# Power_Schematic.net
KiCad netlist of a schematic drawn in Altium Designer
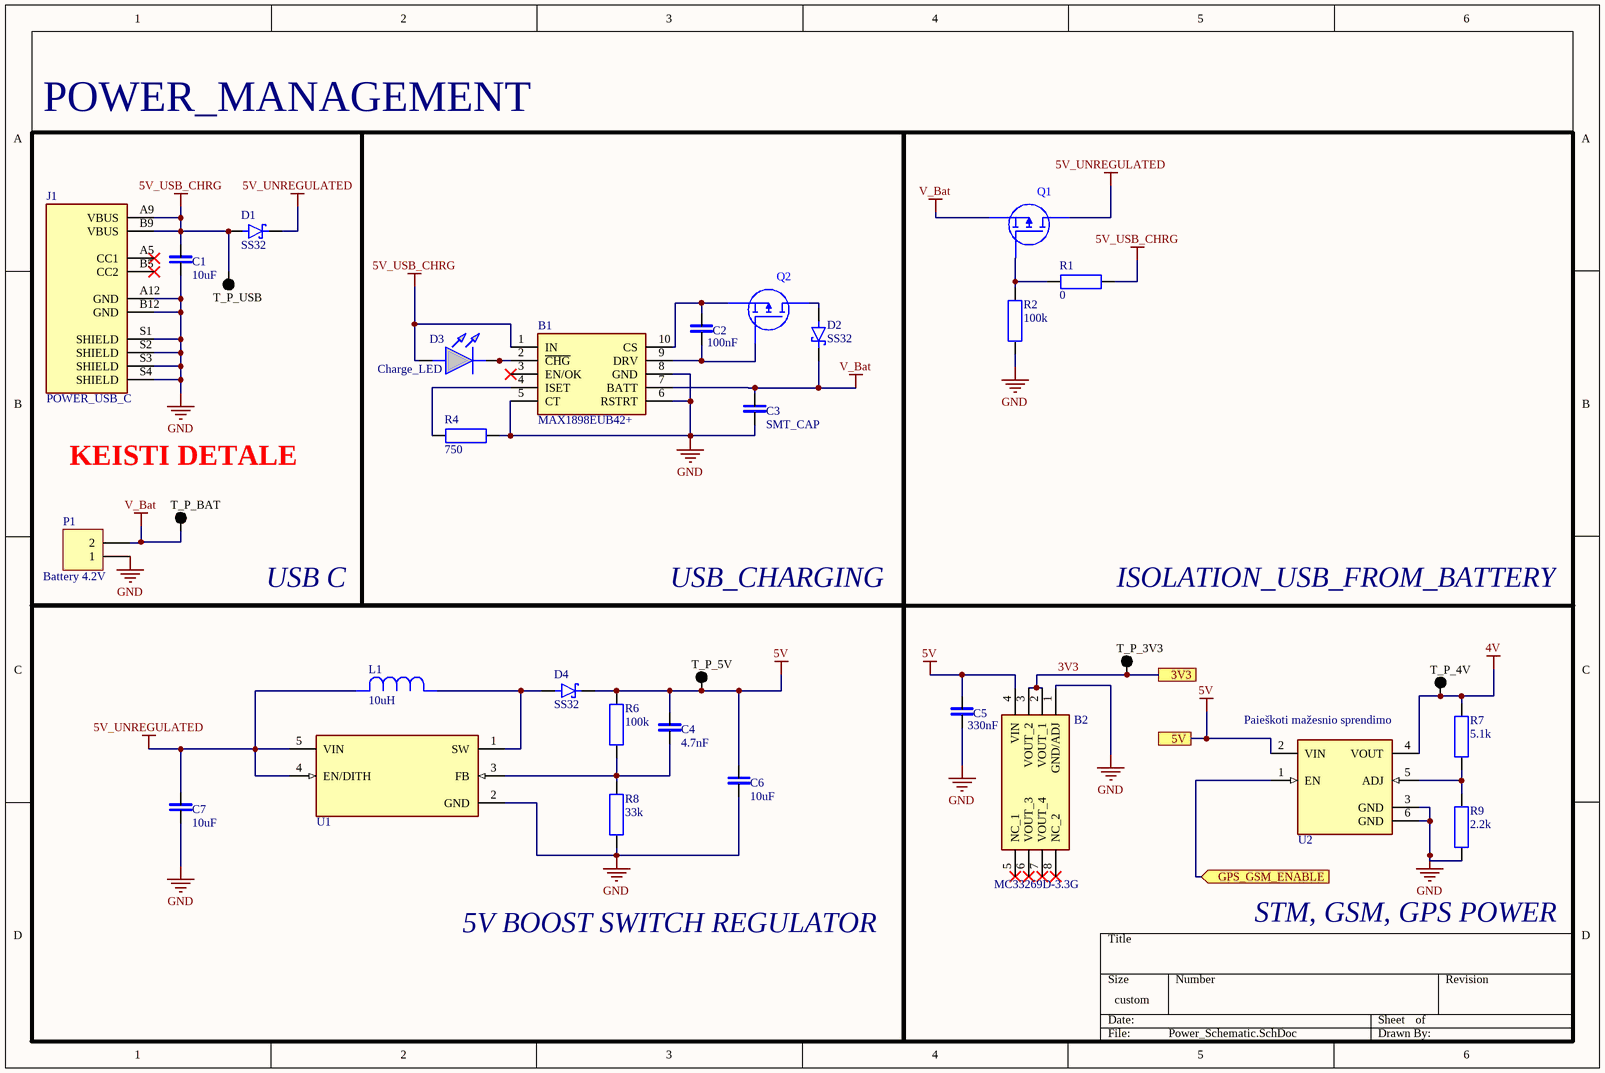
[diagram p0: Power_Schematic.SchDoc]

(export (version "E")
  (design (tool "Eeschema 10.0.6"))
  (components
    (comp (ref "B1")
      (value "MAX1898EUB42+")
      (footprint "MAX1898EUB42")
      (description "Part: MAX1898EUB42+ BATT CHARGER, LI-ION, 4.2V")
      (fields (field (name "MOUSER PART NUMBER") "700-MAX1898EUB42"))
      (libsource (lib "IC") (part "MAX1898EUB42+"))
    )
    (comp (ref "B2")
      (value "MC33269D-3.3G")
      (footprint "3V3Voltage_MC33269D-3.3G")
      (description "Voltage regulator,Part: MC33269D-3.3G, Low Dropout Voltage Regulator, 0.8A 3.3")
      (fields (field (name "MOUSER PART NUMBER") "863-MC33269D-3.3G"))
      (libsource (lib "IC") (part "LDO3V3"))
    )
    (comp (ref "C1")
      (value "10uF")
      (footprint "CAP_0805")
      (fields (field (name "MP") "LD051A270KAB2A"))
      (libsource (lib "Passive_Components") (part "SMT_CAP"))
    )
    (comp (ref "C2")
      (value "100nF")
      (footprint "CAP_0805")
      (fields (field (name "MP") "LD051A270KAB2A"))
      (libsource (lib "Passive_Components") (part "SMT_CAP"))
    )
    (comp (ref "C3")
      (value "SMT_CAP")
      (footprint "CAP_0805")
      (fields (field (name "MP") "LD051A270KAB2A"))
      (libsource (lib "Passive_Components") (part "SMT_CAP"))
    )
    (comp (ref "C4")
      (value "4.7nF")
      (footprint "CAP_0805")
      (fields (field (name "MP") "LD051A270KAB2A"))
      (libsource (lib "Passive_Components") (part "SMT_CAP"))
    )
    (comp (ref "C5")
      (value "330nF")
      (footprint "CAP_0805")
      (fields (field (name "MP") "LD051A270KAB2A"))
      (libsource (lib "Passive_Components") (part "SMT_CAP"))
    )
    (comp (ref "C6")
      (value "10uF")
      (footprint "CAP_0805")
      (fields (field (name "MP") "LD051A270KAB2A"))
      (libsource (lib "Passive_Components") (part "SMT_CAP"))
    )
    (comp (ref "C7")
      (value "10uF")
      (footprint "CAP_0805")
      (fields (field (name "MP") "LD051A270KAB2A"))
      (libsource (lib "Passive_Components") (part "SMT_CAP"))
    )
    (comp (ref "D1")
      (value "SS32")
      (footprint "POWER_SCHOTKY_3A")
      (description "Part: SS32")
      (fields (field (name "MF") "ON Semiconductor"))
      (libsource (lib "Diodes") (part "POWER_SCHOTKY_3A"))
    )
    (comp (ref "D2")
      (value "SS32")
      (footprint "POWER_SCHOTKY_3A")
      (description "Part: SS32")
      (fields (field (name "MF") "ON Semiconductor"))
      (libsource (lib "Diodes") (part "POWER_SCHOTKY_3A"))
    )
    (comp (ref "D3")
      (value "Charge_LED")
      (footprint "LED_0805")
      (description "Part: HSMH-C170")
      (fields
        (field (name "MANUFACTURER_PART_NUMBER") "HSMH-C170")
        (field (name "MOUSER PART NUMBER") "630-HSMH-C170")
      )
      (libsource (lib "Diodes") (part "LED"))
    )
    (comp (ref "D4")
      (value "SS32")
      (footprint "POWER_SCHOTKY_3A")
      (description "Part: SS32")
      (fields (field (name "MF") "ON Semiconductor"))
      (libsource (lib "Diodes") (part "POWER_SCHOTKY_3A"))
    )
    (comp (ref "J1")
      (value "POWER_USB_C")
      (footprint "POWER_USB_C")
      (description "Type C USB Charging Connector part name : USB4515-GF-A_REVA")
      (fields
        (field (name "MF") "Global Connector Technology")
        (field (name "DIGI-KEY_PART_NUMBER") "2073-USB4515-GF-ATR-ND")
      )
      (libsource (lib "Connectors") (part "POWER_USB_C"))
    )
    (comp (ref "L1")
      (value "10uH")
      (footprint "MCSD54-4R7MU")
      (description "Part: MCSD54-4R7MU")
      (fields
        (field (name "MANUFACTURER_PART_NUMBER") "MCSD54-4R7MU")
        (field (name "COPYRIGHT") "Copyright (C) 2023 Ultra Librarian. All rights reserved.")
      )
      (libsource (lib "Passive_Components") (part "IND"))
    )
    (comp (ref "P1")
      (value "Battery 4.2V")
      (footprint "HDR1X2")
      (description "Header, 2-Pin")
      (fields (field (name "PUBLISHER") "Altium Limited"))
      (libsource (lib "Miscellaneous Connectors") (part "Header 2"))
    )
    (comp (ref "Q1")
      (value "MOSFET Pch -45V -4.5A")
      (footprint "P_CHANNEL_POWER_RD3H045SPTL1")
      (description "Part: RD3H045SPTL1")
      (fields
        (field (name "MANUFACTURER_PART_NUMBER") "RD3H045SPTL1")
        (field (name "MOUSER_PART_NUMBER") "755-RD3H045SPTL1")
      )
      (libsource (lib "Transistors") (part "P_CHANNEL_POWER 4.5A RD3H045SPTL1"))
    )
    (comp (ref "Q2")
      (value "MOSFET Pch -45V -4.5A")
      (footprint "P_CHANNEL_POWER_RD3H045SPTL1")
      (description "Part: RD3H045SPTL1")
      (fields
        (field (name "MANUFACTURER_PART_NUMBER") "RD3H045SPTL1")
        (field (name "MOUSER_PART_NUMBER") "755-RD3H045SPTL1")
      )
      (libsource (lib "Transistors") (part "P_CHANNEL_POWER 4.5A RD3H045SPTL1"))
    )
    (comp (ref "R1")
      (value "0")
      (footprint "RES_0805")
      (fields
        (field (name "MP") "2-2176053-0")
        (field (name "TOLERANCE") "1%")
        (field (name "MF") "TE Connectivity")
      )
      (libsource (lib "Passive_Components") (part "SMT_RES"))
    )
    (comp (ref "R2")
      (value "100k")
      (footprint "RES_0805")
      (fields
        (field (name "MP") "2-2176053-0")
        (field (name "TOLERANCE") "1%")
        (field (name "MF") "TE Connectivity")
      )
      (libsource (lib "Passive_Components") (part "SMT_RES"))
    )
    (comp (ref "R4")
      (value "750")
      (footprint "RES_0805")
      (fields
        (field (name "MP") "2-2176053-0")
        (field (name "TOLERANCE") "1%")
        (field (name "MF") "TE Connectivity")
      )
      (libsource (lib "Passive_Components") (part "SMT_RES"))
    )
    (comp (ref "R6")
      (value "100k")
      (footprint "RES_0805")
      (fields
        (field (name "MP") "2-2176053-0")
        (field (name "TOLERANCE") "1%")
        (field (name "MF") "TE Connectivity")
      )
      (libsource (lib "Passive_Components") (part "SMT_RES"))
    )
    (comp (ref "R7")
      (value "5.1k")
      (footprint "RES_0805")
      (fields
        (field (name "MP") "2-2176053-0")
        (field (name "TOLERANCE") "1%")
        (field (name "MF") "TE Connectivity")
      )
      (libsource (lib "Passive_Components") (part "SMT_RES"))
    )
    (comp (ref "R8")
      (value "33k")
      (footprint "RES_0805")
      (fields
        (field (name "MP") "2-2176053-0")
        (field (name "TOLERANCE") "1%")
        (field (name "MF") "TE Connectivity")
      )
      (libsource (lib "Passive_Components") (part "SMT_RES"))
    )
    (comp (ref "R9")
      (value "2.2k")
      (footprint "RES_0805")
      (fields
        (field (name "MP") "2-2176053-0")
        (field (name "TOLERANCE") "1%")
        (field (name "MF") "TE Connectivity")
      )
      (libsource (lib "Passive_Components") (part "SMT_RES"))
    )
    (comp (ref "T_P1")
      (value "T_P_USB")
      (footprint "T_P")
      (description "Test_point")
      (libsource (lib "Extras") (part "T_P"))
    )
    (comp (ref "T_P2")
      (value "T_P_BAT")
      (footprint "T_P")
      (description "Test_point")
      (libsource (lib "Extras") (part "T_P"))
    )
    (comp (ref "T_P3")
      (value "T_P_3V3")
      (footprint "T_P")
      (description "Test_point")
      (libsource (lib "Extras") (part "T_P"))
    )
    (comp (ref "T_P4")
      (value "T_P_5V")
      (footprint "T_P")
      (description "Test_point")
      (libsource (lib "Extras") (part "T_P"))
    )
    (comp (ref "T_P5")
      (value "T_P_4V")
      (footprint "T_P")
      (description "Test_point")
      (libsource (lib "Extras") (part "T_P"))
    )
    (comp (ref "U1")
      (value "Switch Voltage Regulator MIC2250-1YD5-TR")
      (footprint "Switching_MIC2250-1YD5-TR")
      (description "Part: MIC2250-1YD5-TR\r\n2.5V to 5.5 V input \r\n1.24V to 32V output")
      (libsource (lib "IC") (part "Switch Voltage Regulator MIC2250-1YD5-TR"))
    )
    (comp (ref "U2")
      (value "1.24V-5V MIC37252WR")
      (footprint "1V24_5V_MIC37252WR")
      (description "Part: MIC37252WR")
      (libsource (lib "IC") (part "1.24V-5V MIC37252WR"))
    )
  )
  (nets
    (net (code "1") (name "/3V3") (class "Default")
      (node (ref "B2") (pin "2") (pinfunction "VOUT_1_2") (pintype "passive"))
      (node (ref "B2") (pin "3") (pinfunction "VOUT_2_3") (pintype "passive"))
      (node (ref "T_P3") (pin "1") (pintype "passive"))
    )
    (net (code "2") (name "/GPS_GSM_ENABLE") (class "Default")
      (node (ref "U2") (pin "1") (pinfunction "EN_1") (pintype "input"))
    )
    (net (code "3") (name "4V") (class "Default")
      (node (ref "R7") (pin "2") (pinfunction "2_2") (pintype "passive"))
      (node (ref "T_P5") (pin "1") (pintype "passive"))
      (node (ref "U2") (pin "4") (pinfunction "VOUT_4") (pintype "power_in"))
    )
    (net (code "4") (name "5V") (class "Default")
      (node (ref "B2") (pin "4") (pinfunction "VIN_4") (pintype "passive"))
      (node (ref "C4") (pin "2") (pinfunction "2_2") (pintype "passive"))
      (node (ref "C5") (pin "2") (pinfunction "2_2") (pintype "passive"))
      (node (ref "C6") (pin "2") (pinfunction "2_2") (pintype "passive"))
      (node (ref "D4") (pin "C") (pinfunction "K_C") (pintype "passive"))
      (node (ref "R6") (pin "2") (pinfunction "2_2") (pintype "passive"))
      (node (ref "T_P4") (pin "1") (pintype "passive"))
      (node (ref "U2") (pin "2") (pinfunction "VIN_2") (pintype "power_in"))
    )
    (net (code "5") (name "5V_UNREGULATED") (class "Default")
      (node (ref "C7") (pin "2") (pinfunction "2_2") (pintype "passive"))
      (node (ref "D1") (pin "C") (pinfunction "K_C") (pintype "passive"))
      (node (ref "L1") (pin "2") (pinfunction "2_2") (pintype "passive"))
      (node (ref "Q1") (pin "2") (pinfunction "D_2") (pintype "passive"))
      (node (ref "U1") (pin "4") (pinfunction "EN/DITH_4") (pintype "input"))
      (node (ref "U1") (pin "5") (pinfunction "VIN_5") (pintype "power_in"))
    )
    (net (code "6") (name "5V_USB_CHRG") (class "Default")
      (node (ref "B1") (pin "1") (pinfunction "IN_1") (pintype "passive"))
      (node (ref "C1") (pin "2") (pinfunction "2_2") (pintype "passive"))
      (node (ref "D1") (pin "A") (pinfunction "A_A") (pintype "passive"))
      (node (ref "D3") (pin "2") (pinfunction "A_2") (pintype "passive"))
      (node (ref "J1") (pin "A9") (pinfunction "VBUS_A9") (pintype "power_in"))
      (node (ref "J1") (pin "B9") (pinfunction "VBUS_B9") (pintype "power_in"))
      (node (ref "R1") (pin "2") (pinfunction "2_2") (pintype "passive"))
      (node (ref "T_P1") (pin "1") (pintype "passive"))
    )
    (net (code "7") (name "GND") (class "Default")
      (node (ref "B1") (pin "5") (pinfunction "CT_5") (pintype "passive"))
      (node (ref "B1") (pin "6") (pinfunction "RSTRT_6") (pintype "passive"))
      (node (ref "B1") (pin "8") (pinfunction "GND_8") (pintype "passive"))
      (node (ref "B2") (pin "1") (pinfunction "GND/ADJ_1") (pintype "passive"))
      (node (ref "C1") (pin "1") (pinfunction "1_1") (pintype "passive"))
      (node (ref "C3") (pin "1") (pinfunction "1_1") (pintype "passive"))
      (node (ref "C5") (pin "1") (pinfunction "1_1") (pintype "passive"))
      (node (ref "C6") (pin "1") (pinfunction "1_1") (pintype "passive"))
      (node (ref "C7") (pin "1") (pinfunction "1_1") (pintype "passive"))
      (node (ref "J1") (pin "A12") (pinfunction "GND_A12") (pintype "power_in"))
      (node (ref "J1") (pin "B12") (pinfunction "GND_B12") (pintype "power_in"))
      (node (ref "J1") (pin "S1") (pinfunction "SHIELD_S1") (pintype "power_in"))
      (node (ref "J1") (pin "S2") (pinfunction "SHIELD_S2") (pintype "power_in"))
      (node (ref "J1") (pin "S3") (pinfunction "SHIELD_S3") (pintype "power_in"))
      (node (ref "J1") (pin "S4") (pinfunction "SHIELD_S4") (pintype "power_in"))
      (node (ref "P1") (pin "1") (pinfunction "1_1") (pintype "passive"))
      (node (ref "R2") (pin "1") (pinfunction "1_1") (pintype "passive"))
      (node (ref "R4") (pin "2") (pinfunction "2_2") (pintype "passive"))
      (node (ref "R8") (pin "1") (pinfunction "1_1") (pintype "passive"))
      (node (ref "R9") (pin "1") (pinfunction "1_1") (pintype "passive"))
      (node (ref "U1") (pin "2") (pinfunction "GND_2") (pintype "power_in"))
      (node (ref "U2") (pin "3") (pinfunction "GND_3") (pintype "power_in"))
      (node (ref "U2") (pin "6") (pinfunction "GND_6") (pintype "power_in"))
    )
    (net (code "8") (name "Net-(B1-CS)") (class "Default")
      (node (ref "B1") (pin "10") (pinfunction "CS_10") (pintype "passive"))
      (node (ref "C2") (pin "2") (pinfunction "2_2") (pintype "passive"))
      (node (ref "Q2") (pin "3") (pinfunction "S_3") (pintype "passive"))
    )
    (net (code "9") (name "Net-(B1-DRV)") (class "Default")
      (node (ref "B1") (pin "9") (pinfunction "DRV_9") (pintype "passive"))
      (node (ref "C2") (pin "1") (pinfunction "1_1") (pintype "passive"))
      (node (ref "Q2") (pin "1") (pinfunction "G_1") (pintype "passive"))
    )
    (net (code "10") (name "Net-(B1-ISET)") (class "Default")
      (node (ref "B1") (pin "4") (pinfunction "ISET_4") (pintype "passive"))
      (node (ref "R4") (pin "1") (pinfunction "1_1") (pintype "passive"))
    )
    (net (code "11") (name "Net-(B1-~{CHG})") (class "Default")
      (node (ref "B1") (pin "2") (pinfunction "~{CHG}_2") (pintype "passive"))
      (node (ref "D3") (pin "1") (pinfunction "K_1") (pintype "passive"))
    )
    (net (code "12") (name "Net-(Q1-G)") (class "Default")
      (node (ref "Q1") (pin "1") (pinfunction "G_1") (pintype "passive"))
      (node (ref "R1") (pin "1") (pinfunction "1_1") (pintype "passive"))
      (node (ref "R2") (pin "2") (pinfunction "2_2") (pintype "passive"))
    )
    (net (code "13") (name "Net-(Q2-D)") (class "Default")
      (node (ref "D2") (pin "A") (pinfunction "A_A") (pintype "passive"))
      (node (ref "Q2") (pin "2") (pinfunction "D_2") (pintype "passive"))
    )
    (net (code "14") (name "Net-(U1-FB)") (class "Default")
      (node (ref "C4") (pin "1") (pinfunction "1_1") (pintype "passive"))
      (node (ref "R6") (pin "1") (pinfunction "1_1") (pintype "passive"))
      (node (ref "R8") (pin "2") (pinfunction "2_2") (pintype "passive"))
      (node (ref "U1") (pin "3") (pinfunction "FB_3") (pintype "input"))
    )
    (net (code "15") (name "Net-(U1-SW)") (class "Default")
      (node (ref "D4") (pin "A") (pinfunction "A_A") (pintype "passive"))
      (node (ref "L1") (pin "1") (pinfunction "1_1") (pintype "passive"))
      (node (ref "U1") (pin "1") (pinfunction "SW_1") (pintype "passive"))
    )
    (net (code "16") (name "Net-(U2-ADJ)") (class "Default")
      (node (ref "R7") (pin "1") (pinfunction "1_1") (pintype "passive"))
      (node (ref "R9") (pin "2") (pinfunction "2_2") (pintype "passive"))
      (node (ref "U2") (pin "5") (pinfunction "ADJ_5") (pintype "input"))
    )
    (net (code "17") (name "V_Bat") (class "Default")
      (node (ref "B1") (pin "7") (pinfunction "BATT_7") (pintype "passive"))
      (node (ref "C3") (pin "2") (pinfunction "2_2") (pintype "passive"))
      (node (ref "D2") (pin "C") (pinfunction "K_C") (pintype "passive"))
      (node (ref "P1") (pin "2") (pinfunction "2_2") (pintype "passive"))
      (node (ref "Q1") (pin "3") (pinfunction "S_3") (pintype "passive"))
      (node (ref "T_P2") (pin "1") (pintype "passive"))
    )
    (net (code "18") (name "unconnected-(B1-EN{slash}OK-Pad3)") (class "Default")
      (node (ref "B1") (pin "3") (pinfunction "EN/OK_3") (pintype "passive+no_connect"))
    )
    (net (code "19") (name "unconnected-(B2-NC_1-Pad5)") (class "Default")
      (node (ref "B2") (pin "5") (pinfunction "NC_1_5") (pintype "passive+no_connect"))
    )
    (net (code "20") (name "unconnected-(B2-NC_2-Pad8)") (class "Default")
      (node (ref "B2") (pin "8") (pinfunction "NC_2_8") (pintype "passive+no_connect"))
    )
    (net (code "21") (name "unconnected-(B2-VOUT_3-Pad6)") (class "Default")
      (node (ref "B2") (pin "6") (pinfunction "VOUT_3_6") (pintype "passive+no_connect"))
    )
    (net (code "22") (name "unconnected-(B2-VOUT_4-Pad7)") (class "Default")
      (node (ref "B2") (pin "7") (pinfunction "VOUT_4_7") (pintype "passive+no_connect"))
    )
    (net (code "23") (name "unconnected-(J1-CC1-PadA5)") (class "Default")
      (node (ref "J1") (pin "A5") (pinfunction "CC1_A5") (pintype "passive+no_connect"))
    )
    (net (code "24") (name "unconnected-(J1-CC2-PadB5)") (class "Default")
      (node (ref "J1") (pin "B5") (pinfunction "CC2_B5") (pintype "passive+no_connect"))
    )
  )
)
